# Sheet1.net
KiCad netlist of a schematic drawn in Altium Designer
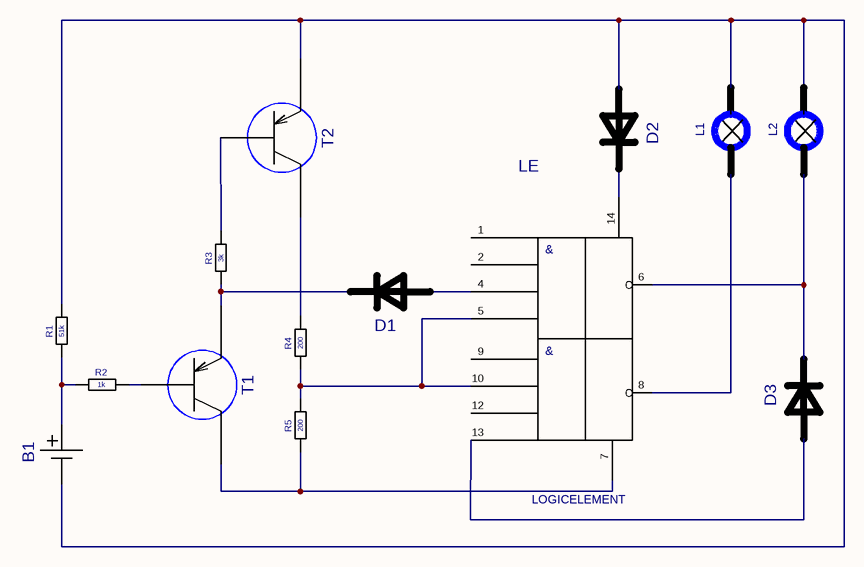
[diagram p0: Sheet1.SCHDOC]

(export (version "E")
  (design (tool "Eeschema 10.0.6"))
  (components
    (comp (ref "B1")
      (value "KRONA")
      (footprint "KRONA")
      (fields (field (name "AUTHOR") "pcbdesigner.ru"))
      (libsource (lib "*") (part "KRONA"))
    )
    (comp (ref "D1") (value "DIODE") (footprint "DIODE") (libsource (lib "*") (part "DIODE")))
    (comp (ref "D2") (value "DIODE") (footprint "DIODE") (libsource (lib "*") (part "DIODE")))
    (comp (ref "D3") (value "DIODE") (footprint "DIODE") (libsource (lib "*") (part "DIODE")))
    (comp (ref "L1") (value "СМН6.3-20-2") (footprint "HL_MINI") (libsource (lib "*") (part "СМН6.3-20-2")))
    (comp (ref "L2") (value "СМН6.3-20-2") (footprint "HL_MINI") (libsource (lib "*") (part "СМН6.3-20-2")))
    (comp (ref "LE")
      (value "LOGICELEMENT")
      (footprint "LOGICELEMENT")
      (libsource (lib "*") (part "LOGICELEMENT"))
    )
    (comp (ref "R1")
      (value "51k")
      (footprint "RES")
      (description "Resistor")
      (fields (field (name "Comment") "RES"))
      (libsource (lib "*") (part "RES"))
    )
    (comp (ref "R2")
      (value "1k")
      (footprint "RES")
      (description "Resistor")
      (fields (field (name "Comment") "RES"))
      (libsource (lib "*") (part "RES"))
    )
    (comp (ref "R3")
      (value "3k")
      (footprint "RES")
      (description "Resistor")
      (fields (field (name "Comment") "RES"))
      (libsource (lib "*") (part "RES"))
    )
    (comp (ref "R4")
      (value "200")
      (footprint "RES")
      (description "Resistor")
      (fields (field (name "Comment") "RES"))
      (libsource (lib "*") (part "RES"))
    )
    (comp (ref "R5")
      (value "200")
      (footprint "RES")
      (description "Resistor")
      (fields (field (name "Comment") "RES"))
      (libsource (lib "*") (part "RES"))
    )
    (comp (ref "T1") (value "PNP") (footprint "KT-27 (2002)") (libsource (lib "*") (part "PNP")))
    (comp (ref "T2") (value "PNP") (footprint "KT-27 (2002)") (libsource (lib "*") (part "PNP")))
  )
  (nets
    (net (code "1") (name "Net-(B1-1)") (class "Default")
      (node (ref "B1") (pin "minus") (pinfunction "1_minus") (pintype "passive"))
      (node (ref "D2") (pin "1") (pintype "passive"))
      (node (ref "L1") (pin "2") (pinfunction "2_2") (pintype "passive"))
      (node (ref "L2") (pin "2") (pinfunction "2_2") (pintype "passive"))
      (node (ref "R1") (pin "1") (pintype "passive"))
      (node (ref "T2") (pin "1") (pintype "passive"))
    )
    (net (code "2") (name "Net-(B1-2)") (class "Default")
      (node (ref "B1") (pin "plus") (pinfunction "2_plus") (pintype "passive"))
      (node (ref "R1") (pin "2") (pintype "passive"))
      (node (ref "R2") (pin "2") (pintype "passive"))
    )
    (net (code "3") (name "Net-(D1-Pad1)") (class "Default")
      (node (ref "D1") (pin "1") (pintype "passive"))
      (node (ref "LE") (pin "4") (pinfunction "0_4") (pintype "passive"))
    )
    (net (code "4") (name "Net-(D1-Pad2)") (class "Default")
      (node (ref "D1") (pin "2") (pintype "passive"))
      (node (ref "R3") (pin "2") (pintype "passive"))
      (node (ref "T1") (pin "1") (pintype "passive"))
    )
    (net (code "5") (name "Net-(D2-Pad2)") (class "Default")
      (node (ref "D2") (pin "2") (pintype "passive"))
      (node (ref "LE") (pin "14") (pinfunction "0_14") (pintype "passive"))
    )
    (net (code "6") (name "Net-(D3-Pad1)") (class "Default")
      (node (ref "D3") (pin "1") (pintype "passive"))
      (node (ref "LE") (pin "13") (pinfunction "0_13") (pintype "passive"))
    )
    (net (code "7") (name "Net-(D3-Pad2)") (class "Default")
      (node (ref "D3") (pin "2") (pintype "passive"))
      (node (ref "L2") (pin "1") (pinfunction "1_1") (pintype "passive"))
      (node (ref "LE") (pin "6") (pinfunction "0_6") (pintype "passive"))
    )
    (net (code "8") (name "Net-(L1-Pad1)") (class "Default")
      (node (ref "L1") (pin "1") (pinfunction "1_1") (pintype "passive"))
      (node (ref "LE") (pin "8") (pinfunction "0_8") (pintype "passive"))
    )
    (net (code "9") (name "Net-(LE-0-Pad7)") (class "Default")
      (node (ref "LE") (pin "7") (pinfunction "0_7") (pintype "passive"))
      (node (ref "R5") (pin "2") (pintype "passive"))
      (node (ref "T1") (pin "3") (pintype "passive"))
    )
    (net (code "10") (name "Net-(LE-0-Pad10)") (class "Default")
      (node (ref "LE") (pin "10") (pinfunction "0_10") (pintype "passive"))
      (node (ref "LE") (pin "5") (pinfunction "0_5") (pintype "passive"))
      (node (ref "R4") (pin "2") (pintype "passive"))
      (node (ref "R5") (pin "1") (pintype "passive"))
    )
    (net (code "11") (name "Net-(R2-Pad1)") (class "Default")
      (node (ref "R2") (pin "1") (pintype "passive"))
      (node (ref "T1") (pin "2") (pintype "passive"))
    )
    (net (code "12") (name "Net-(R3-Pad1)") (class "Default")
      (node (ref "R3") (pin "1") (pintype "passive"))
      (node (ref "T2") (pin "2") (pintype "passive"))
    )
    (net (code "13") (name "Net-(R4-Pad1)") (class "Default")
      (node (ref "R4") (pin "1") (pintype "passive"))
      (node (ref "T2") (pin "3") (pintype "passive"))
    )
    (net (code "14") (name "unconnected-(B1-Pad1)") (class "Default")
      (node (ref "B1") (pin "1") (pintype "passive"))
    )
    (net (code "15") (name "unconnected-(B1-Pad2)") (class "Default")
      (node (ref "B1") (pin "2") (pintype "passive"))
    )
    (net (code "16") (name "unconnected-(LE-0-Pad1)") (class "Default")
      (node (ref "LE") (pin "1") (pinfunction "0_1") (pintype "passive"))
    )
    (net (code "17") (name "unconnected-(LE-0-Pad2)") (class "Default")
      (node (ref "LE") (pin "2") (pinfunction "0_2") (pintype "passive"))
    )
    (net (code "18") (name "unconnected-(LE-0-Pad9)") (class "Default")
      (node (ref "LE") (pin "9") (pinfunction "0_9") (pintype "passive"))
    )
    (net (code "19") (name "unconnected-(LE-0-Pad12)") (class "Default")
      (node (ref "LE") (pin "12") (pinfunction "0_12") (pintype "passive"))
    )
  )
)
